# main.net
KiCad netlist of a schematic drawn in Altium Designer
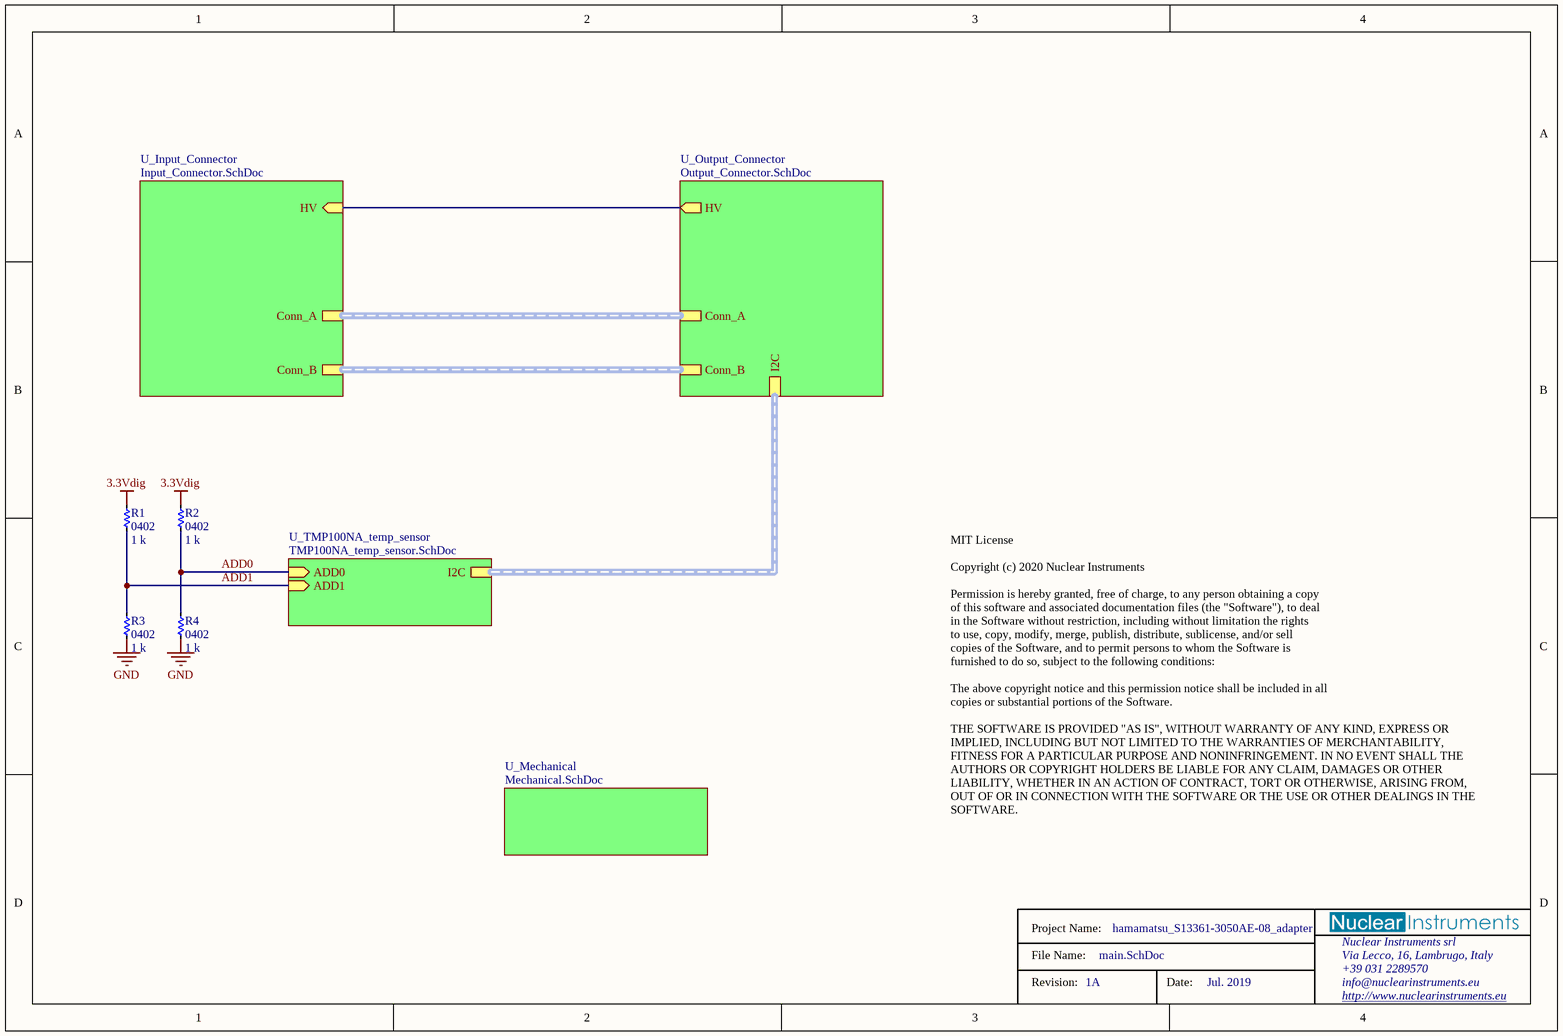
[diagram p0: main.SchDoc]

(export (version "E")
  (design (tool "Eeschema 10.0.6"))
  (components
    (comp (ref "R1")
      (value "0402")
      (footprint "RESSMD0402")
      (fields (field (name "ALTIUM_VALUE") "1 k"))
      (libsource (lib "altium-import") (part "root_0_RES0402-1k_"))
    )
    (comp (ref "R2")
      (value "0402")
      (footprint "RESSMD0402")
      (fields (field (name "ALTIUM_VALUE") "1 k"))
      (libsource (lib "altium-import") (part "root_0_RES0402-1k_"))
    )
    (comp (ref "R3")
      (value "0402")
      (footprint "RESSMD0402")
      (fields (field (name "ALTIUM_VALUE") "1 k"))
      (libsource (lib "altium-import") (part "root_0_RES0402-1k_"))
    )
    (comp (ref "R4")
      (value "0402")
      (footprint "RESSMD0402")
      (fields (field (name "ALTIUM_VALUE") "1 k"))
      (libsource (lib "altium-import") (part "root_0_RES0402-1k_"))
    )
  )
  (nets
    (net (code "1") (name "/ADD0") (class "Default")
      (node (ref "R2") (pin "2") (pinfunction "2_2") (pintype "passive"))
      (node (ref "R4") (pin "1") (pinfunction "1_1") (pintype "passive"))
    )
    (net (code "2") (name "/ADD1") (class "Default")
      (node (ref "R1") (pin "2") (pinfunction "2_2") (pintype "passive"))
      (node (ref "R3") (pin "1") (pinfunction "1_1") (pintype "passive"))
    )
    (net (code "7") (name "3.3Vdig") (class "Default")
      (node (ref "R1") (pin "1") (pinfunction "1_1") (pintype "passive"))
      (node (ref "R2") (pin "1") (pinfunction "1_1") (pintype "passive"))
    )
    (net (code "8") (name "GND") (class "Default")
      (node (ref "R3") (pin "2") (pinfunction "2_2") (pintype "passive"))
      (node (ref "R4") (pin "2") (pinfunction "2_2") (pintype "passive"))
    )
  )
)
